# lv-supply.net
KiCad netlist of a schematic drawn in Altium Designer
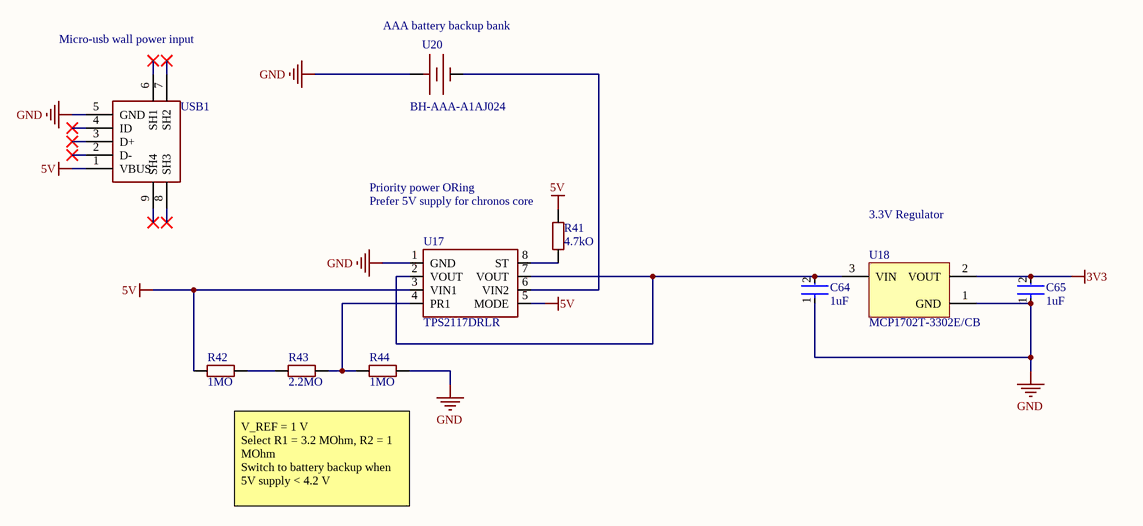
[diagram p0: lv-supply.SchDoc]

(export (version "E")
  (design (tool "Eeschema 10.0.6"))
  (components
    (comp (ref "C64")
      (value "CL05A105KA5NQNC")
      (footprint "FP-CL542-IPC_C")
      (description "Cap Ceramic 1uF 25V X5R ±10% SMD 0402 +85°C Paper T/R")
      (fields (field (name "CAPACITANCE") "1uF") (field (name "TOLERANCE") "10%"))
      (libsource (lib "Altium Content Vault") (part "b4654b650e69147ec39a6b967a45e02"))
    )
    (comp (ref "C65")
      (value "CL05A105KA5NQNC")
      (footprint "FP-CL542-IPC_C")
      (description "Cap Ceramic 1uF 25V X5R ±10% SMD 0402 +85°C Paper T/R")
      (fields (field (name "CAPACITANCE") "1uF") (field (name "TOLERANCE") "10%"))
      (libsource (lib "Altium Content Vault") (part "b4654b650e69147ec39a6b967a45e02"))
    )
    (comp (ref "R41")
      (value "4.7kO")
      (footprint "0402WGF4701TCE")
      (fields
        (field (name "JLCPCB PART #") "C25900")
        (field (name "MANUFACTURER PART NUMBER") "0402WGF4701TCE")
        (field (name "MANUFACTURER") "UNI-ROYAL(Uniroyal Elec)")
      )
      (libsource (lib "0402WGF4701TCE") (part "0402WGF4701TCE"))
    )
    (comp (ref "R42")
      (value "1MO")
      (footprint "0402WGF1004TCE")
      (fields
        (field (name "JLCPCB PART #") "C26083")
        (field (name "MANUFACTURER PART NUMBER") "0402WGF1004TCE")
        (field (name "MANUFACTURER") "UNI-ROYAL(Uniroyal Elec)")
      )
      (libsource (lib "0402WGF1004TCE") (part "0402WGF1004TCE"))
    )
    (comp (ref "R43")
      (value "2.2MO")
      (footprint "0603WAF2204T5E")
      (fields
        (field (name "JLCPCB PART #") "C22938")
        (field (name "MANUFACTURER PART NUMBER") "0603WAF2204T5E")
        (field (name "MANUFACTURER") "UNI-ROYAL(Uniroyal Elec)")
      )
      (libsource (lib "0603WAF2204T5E") (part "0603WAF2204T5E"))
    )
    (comp (ref "R44")
      (value "1MO")
      (footprint "0402WGF1004TCE")
      (fields
        (field (name "JLCPCB PART #") "C26083")
        (field (name "MANUFACTURER PART NUMBER") "0402WGF1004TCE")
        (field (name "MANUFACTURER") "UNI-ROYAL(Uniroyal Elec)")
      )
      (libsource (lib "0402WGF1004TCE") (part "0402WGF1004TCE"))
    )
    (comp (ref "U17")
      (value "TPS2117DRLR")
      (footprint "TPS2117DRLR")
      (fields (field (name "JLCPCB PART #") "C22399676") (field (name "MANUFACTURER") "Texas Instruments"))
      (libsource (lib "TPS2117DRLR") (part "TPS2117DRLR"))
    )
    (comp (ref "U18")
      (value "MCP1702T-3302E/CB")
      (footprint "SOT-23A-CB3_N")
      (description "250 mA Low Quiescent Current LDO Regulator, 3-Pin SOT-23A, Extended Temperature, Tape and Reel")
      (libsource (lib "Altium Content Vault") (part "PM-LINEREG-MCP1702-IL3"))
    )
    (comp (ref "U20")
      (value "BH-AAA-A1AJ024")
      (footprint "BH-AAA-A1AJ024")
      (description "Battery Connectors. -10~100C Battery holder Nickel plated No. 7 - ROHS")
      (fields (field (name "JLCPCB PART #") "C5290193") (field (name "MANUFACTURER") "MYOUNG"))
      (libsource (lib "BH-AAA-A1AJ024") (part "BH-AAA-A1AJ024"))
    )
    (comp (ref "USB1")
      (value "MicroXNJ")
      (footprint "MicroXNJ")
      (fields (field (name "JLCPCB PART #") "C404969") (field (name "MANUFACTURER") "SHOU HAN"))
      (libsource (lib "MicroXNJ") (part "MicroXNJ"))
    )
  )
  (nets
    (net (code "1") (name "3V3") (class "Default")
      (node (ref "C65") (pin "2") (pinfunction "2_2") (pintype "passive"))
      (node (ref "U18") (pin "2") (pinfunction "VOUT_2") (pintype "power_in"))
    )
    (net (code "2") (name "5V") (class "Default")
      (node (ref "R41") (pin "2") (pinfunction "2_2") (pintype "passive"))
      (node (ref "R42") (pin "2") (pinfunction "2_2") (pintype "passive"))
      (node (ref "U17") (pin "3") (pinfunction "VIN1_3") (pintype "passive"))
      (node (ref "U17") (pin "5") (pinfunction "MODE_5") (pintype "passive"))
      (node (ref "USB1") (pin "1") (pinfunction "VBUS_1") (pintype "passive"))
    )
    (net (code "3") (name "GND") (class "Default")
      (node (ref "C64") (pin "1") (pinfunction "1_1") (pintype "passive"))
      (node (ref "C65") (pin "1") (pinfunction "1_1") (pintype "passive"))
      (node (ref "R44") (pin "1") (pinfunction "1_1") (pintype "passive"))
      (node (ref "U17") (pin "1") (pinfunction "GND_1") (pintype "passive"))
      (node (ref "U18") (pin "1") (pinfunction "GND_1") (pintype "power_in"))
      (node (ref "U20") (pin "2") (pinfunction "+_2") (pintype "passive"))
      (node (ref "USB1") (pin "5") (pinfunction "GND_5") (pintype "passive"))
    )
    (net (code "4") (name "Net-(R42-Pad1)") (class "Default")
      (node (ref "R42") (pin "1") (pinfunction "1_1") (pintype "passive"))
      (node (ref "R43") (pin "2") (pinfunction "2_2") (pintype "passive"))
    )
    (net (code "5") (name "Net-(U17-PR1)") (class "Default")
      (node (ref "R43") (pin "1") (pinfunction "1_1") (pintype "passive"))
      (node (ref "R44") (pin "2") (pinfunction "2_2") (pintype "passive"))
      (node (ref "U17") (pin "4") (pinfunction "PR1_4") (pintype "passive"))
    )
    (net (code "6") (name "Net-(U17-ST)") (class "Default")
      (node (ref "R41") (pin "1") (pinfunction "1_1") (pintype "passive"))
      (node (ref "U17") (pin "8") (pinfunction "ST_8") (pintype "passive"))
    )
    (net (code "7") (name "Net-(U17-VIN2)") (class "Default")
      (node (ref "U17") (pin "6") (pinfunction "VIN2_6") (pintype "passive"))
      (node (ref "U20") (pin "1") (pinfunction "-_1") (pintype "passive"))
    )
    (net (code "8") (name "Net-(U18-VIN)") (class "Default")
      (node (ref "C64") (pin "2") (pinfunction "2_2") (pintype "passive"))
      (node (ref "U17") (pin "2") (pinfunction "VOUT_2") (pintype "passive"))
      (node (ref "U17") (pin "7") (pinfunction "VOUT_7") (pintype "passive"))
      (node (ref "U18") (pin "3") (pinfunction "VIN_3") (pintype "power_in"))
    )
    (net (code "9") (name "unconnected-(USB1-D+-Pad3)") (class "Default")
      (node (ref "USB1") (pin "3") (pinfunction "D+_3") (pintype "passive+no_connect"))
    )
    (net (code "10") (name "unconnected-(USB1-D--Pad2)") (class "Default")
      (node (ref "USB1") (pin "2") (pinfunction "D-_2") (pintype "passive+no_connect"))
    )
    (net (code "11") (name "unconnected-(USB1-ID-Pad4)") (class "Default")
      (node (ref "USB1") (pin "4") (pinfunction "ID_4") (pintype "passive+no_connect"))
    )
    (net (code "12") (name "unconnected-(USB1-SH1-Pad6)") (class "Default")
      (node (ref "USB1") (pin "6") (pinfunction "SH1_6") (pintype "passive+no_connect"))
    )
    (net (code "13") (name "unconnected-(USB1-SH2-Pad7)") (class "Default")
      (node (ref "USB1") (pin "7") (pinfunction "SH2_7") (pintype "passive+no_connect"))
    )
    (net (code "14") (name "unconnected-(USB1-SH3-Pad8)") (class "Default")
      (node (ref "USB1") (pin "8") (pinfunction "SH3_8") (pintype "passive+no_connect"))
    )
    (net (code "15") (name "unconnected-(USB1-SH4-Pad9)") (class "Default")
      (node (ref "USB1") (pin "9") (pinfunction "SH4_9") (pintype "passive+no_connect"))
    )
  )
)
